# JTAG.net
KiCad netlist of a schematic drawn in Altium Designer
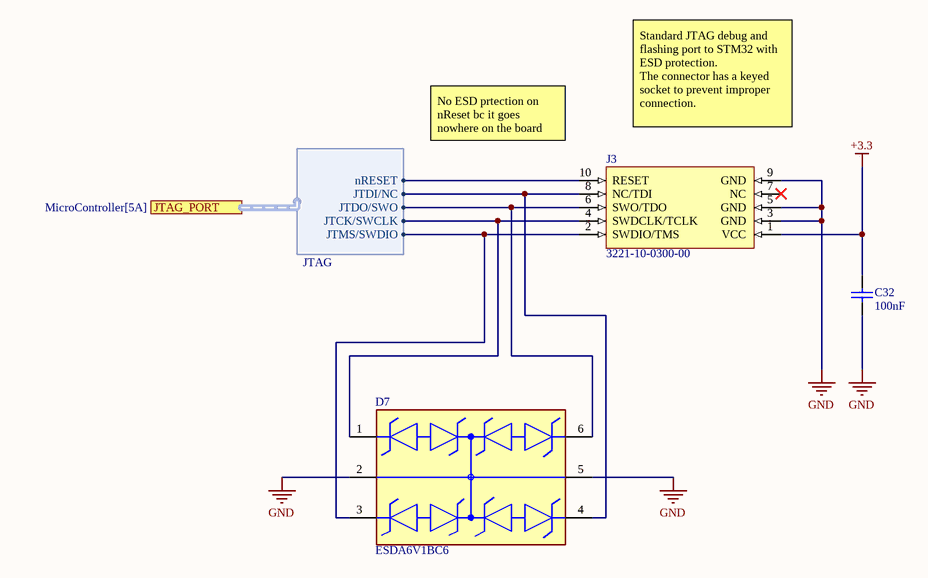
[diagram p0: JTAG.SchDoc]

(export (version "E")
  (design (tool "Eeschema 10.0.6"))
  (components
    (comp (ref "C32")
      (value "100nF")
      (footprint "CAPC1608X90X40ML10T20")
      (description "Chip Capacitor, 0.1uF, +/- 10%, 50 V, 0603 (1608 Metric)")
      (fields (field (name "TOLERANCE") "10%") (field (name "Comment") "Capacitor 0.1uF +/-10% 50 V 0603"))
      (libsource (lib "University of Minnesota - Solar Vehicle Project") (part "Cap"))
    )
    (comp (ref "D7")
      (value "ESDA6V1BC6")
      (footprint "FP-SOT23-6L-IPC_A")
      (description "Trans Voltage Suppressor Diode, 80W, 5V V(RWM), Bidirectional, 4 Element, Silicon")
      (libsource (lib "University of Minnesota - Solar Vehicle Project") (part "3fc8afaed3c8ed0e97b36f4d4f9a65f"))
    )
    (comp (ref "J3")
      (value "3221-10-0300-00")
      (footprint "3221-10-0300-00-Footprint-1")
      (description "JTAG STLINK CONN HEADER SMD 10POS 1.27MM")
      (libsource (lib "University of Minnesota - Solar Vehicle Project") (part "3221-10-0300-00-Symbol-1"))
    )
  )
  (nets
    (net (code "2") (name "+3.3") (class "Default")
      (node (ref "C32") (pin "2") (pinfunction "2_2") (pintype "passive"))
      (node (ref "J3") (pin "1") (pinfunction "VCC_1") (pintype "input"))
    )
    (net (code "3") (name "/JTCK{slash}SWCLK") (class "Default")
      (node (ref "D7") (pin "1") (pinfunction "1_1") (pintype "passive"))
      (node (ref "J3") (pin "4") (pinfunction "SWDCLK/TCLK_4") (pintype "input"))
    )
    (net (code "4") (name "/JTDI{slash}NC") (class "Default")
      (node (ref "D7") (pin "4") (pinfunction "4_4") (pintype "passive"))
      (node (ref "J3") (pin "8") (pinfunction "NC/TDI_8") (pintype "input"))
    )
    (net (code "5") (name "/JTDO{slash}SWO") (class "Default")
      (node (ref "D7") (pin "6") (pinfunction "6_6") (pintype "passive"))
      (node (ref "J3") (pin "6") (pinfunction "SWO/TDO_6") (pintype "input"))
    )
    (net (code "6") (name "/JTMS{slash}SWDIO") (class "Default")
      (node (ref "D7") (pin "3") (pinfunction "3_3") (pintype "passive"))
      (node (ref "J3") (pin "2") (pinfunction "SWDIO/TMS_2") (pintype "input"))
    )
    (net (code "7") (name "/nRESET") (class "Default")
      (node (ref "J3") (pin "10") (pinfunction "RESET_10") (pintype "input"))
    )
    (net (code "9") (name "GND") (class "Default")
      (node (ref "C32") (pin "1") (pinfunction "1_1") (pintype "passive"))
      (node (ref "D7") (pin "2") (pinfunction "2_2") (pintype "passive"))
      (node (ref "D7") (pin "5") (pinfunction "5_5") (pintype "passive"))
      (node (ref "J3") (pin "3") (pinfunction "GND_3") (pintype "input"))
      (node (ref "J3") (pin "5") (pinfunction "GND_5") (pintype "input"))
      (node (ref "J3") (pin "9") (pinfunction "GND_9") (pintype "input"))
    )
    (net (code "10") (name "unconnected-(J3-NC-Pad7)") (class "Default")
      (node (ref "J3") (pin "7") (pinfunction "NC_7") (pintype "input+no_connect"))
    )
  )
)
